# I2C.net
KiCad netlist of a schematic drawn in Altium Designer
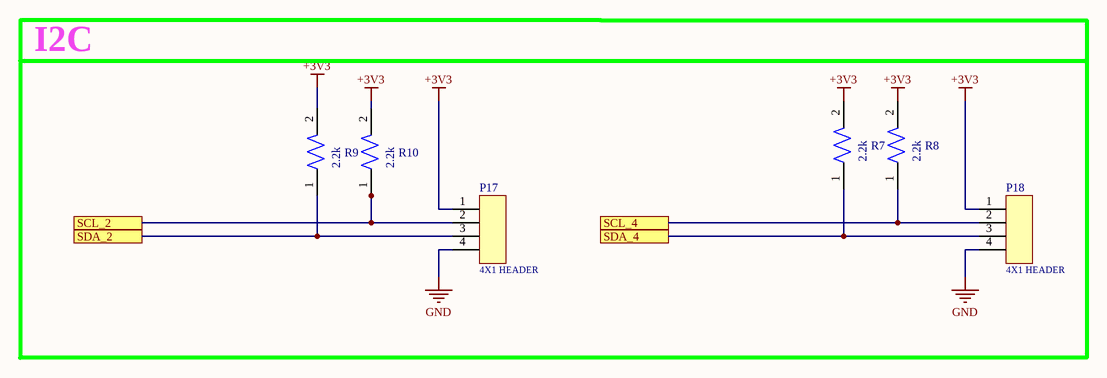
[diagram p0: I2C.SchDoc]

(export (version "E")
  (design (tool "Eeschema 10.0.6"))
  (components
    (comp (ref "P17")
      (value "CONN HEADER SMD R/A 4POS 1.25MM")
      (footprint "DF13-4P-1.25V")
      (description "Conn Shrouded Header HDR 4 POS 1.25mm Solder RA SMD Embossed T/R")
      (fields
        (field (name "MANUFACTURER") "Hirose")
        (field (name "MANUFACTURER PART NUMBER") "DF13-4P-1.25H(21)")
        (field (name "DESIGNED BY") "Süeda KORKMAZ")
      )
      (libsource (lib "Schlib1") (part "DF13-4P-1.25H(21)"))
    )
    (comp (ref "P18")
      (value "CONN HEADER SMD R/A 4POS 1.25MM")
      (footprint "DF13-4P-1.25V")
      (description "Conn Shrouded Header HDR 4 POS 1.25mm Solder RA SMD Embossed T/R")
      (fields
        (field (name "MANUFACTURER") "Hirose")
        (field (name "MANUFACTURER PART NUMBER") "DF13-4P-1.25H(21)")
        (field (name "DESIGNED BY") "Süeda KORKMAZ")
      )
      (libsource (lib "Schlib1") (part "DF13-4P-1.25H(21)"))
    )
    (comp (ref "R7")
      (value "Dip resistor")
      (footprint "Resistor DIP")
      (fields
        (field (name "MANUFACTURER") "Vishay")
        (field (name "MANUFACTURER PART NUMBER") "CRCW06032K20FKEAHP")
        (field (name "TOLERANCE") "1%")
      )
      (libsource (lib "Schlib1") (part "2.2k dip"))
    )
    (comp (ref "R8")
      (value "Dip resistor")
      (footprint "Resistor DIP")
      (fields
        (field (name "MANUFACTURER") "Vishay")
        (field (name "MANUFACTURER PART NUMBER") "CRCW06032K20FKEAHP")
        (field (name "TOLERANCE") "1%")
      )
      (libsource (lib "Schlib1") (part "2.2k dip"))
    )
    (comp (ref "R9")
      (value "Dip resistor")
      (footprint "Resistor DIP")
      (fields
        (field (name "MANUFACTURER") "Vishay")
        (field (name "MANUFACTURER PART NUMBER") "CRCW06032K20FKEAHP")
        (field (name "TOLERANCE") "1%")
      )
      (libsource (lib "Schlib1") (part "2.2k dip"))
    )
    (comp (ref "R10")
      (value "Dip resistor")
      (footprint "Resistor DIP")
      (fields
        (field (name "MANUFACTURER") "Vishay")
        (field (name "MANUFACTURER PART NUMBER") "CRCW06032K20FKEAHP")
        (field (name "TOLERANCE") "1%")
      )
      (libsource (lib "Schlib1") (part "2.2k dip"))
    )
  )
  (nets
    (net (code "1") (name "+3V3") (class "Default")
      (node (ref "P17") (pin "1") (pintype "passive"))
      (node (ref "P18") (pin "1") (pintype "passive"))
      (node (ref "R10") (pin "2") (pintype "passive"))
      (node (ref "R7") (pin "2") (pintype "passive"))
      (node (ref "R8") (pin "2") (pintype "passive"))
      (node (ref "R9") (pin "2") (pintype "passive"))
    )
    (net (code "2") (name "/SCL_2") (class "Default")
      (node (ref "P17") (pin "2") (pintype "passive"))
      (node (ref "R10") (pin "1") (pintype "passive"))
    )
    (net (code "3") (name "/SCL_4") (class "Default")
      (node (ref "P18") (pin "2") (pintype "passive"))
      (node (ref "R8") (pin "1") (pintype "passive"))
    )
    (net (code "4") (name "/SDA_2") (class "Default")
      (node (ref "P17") (pin "3") (pintype "passive"))
      (node (ref "R9") (pin "1") (pintype "passive"))
    )
    (net (code "5") (name "/SDA_4") (class "Default")
      (node (ref "P18") (pin "3") (pintype "passive"))
      (node (ref "R7") (pin "1") (pintype "passive"))
    )
    (net (code "6") (name "GND") (class "Default")
      (node (ref "P17") (pin "4") (pintype "passive"))
      (node (ref "P18") (pin "4") (pintype "passive"))
    )
  )
)
